# NorthStar_SuperCap_V0_2.net
KiCad netlist of a schematic drawn in EAGLE
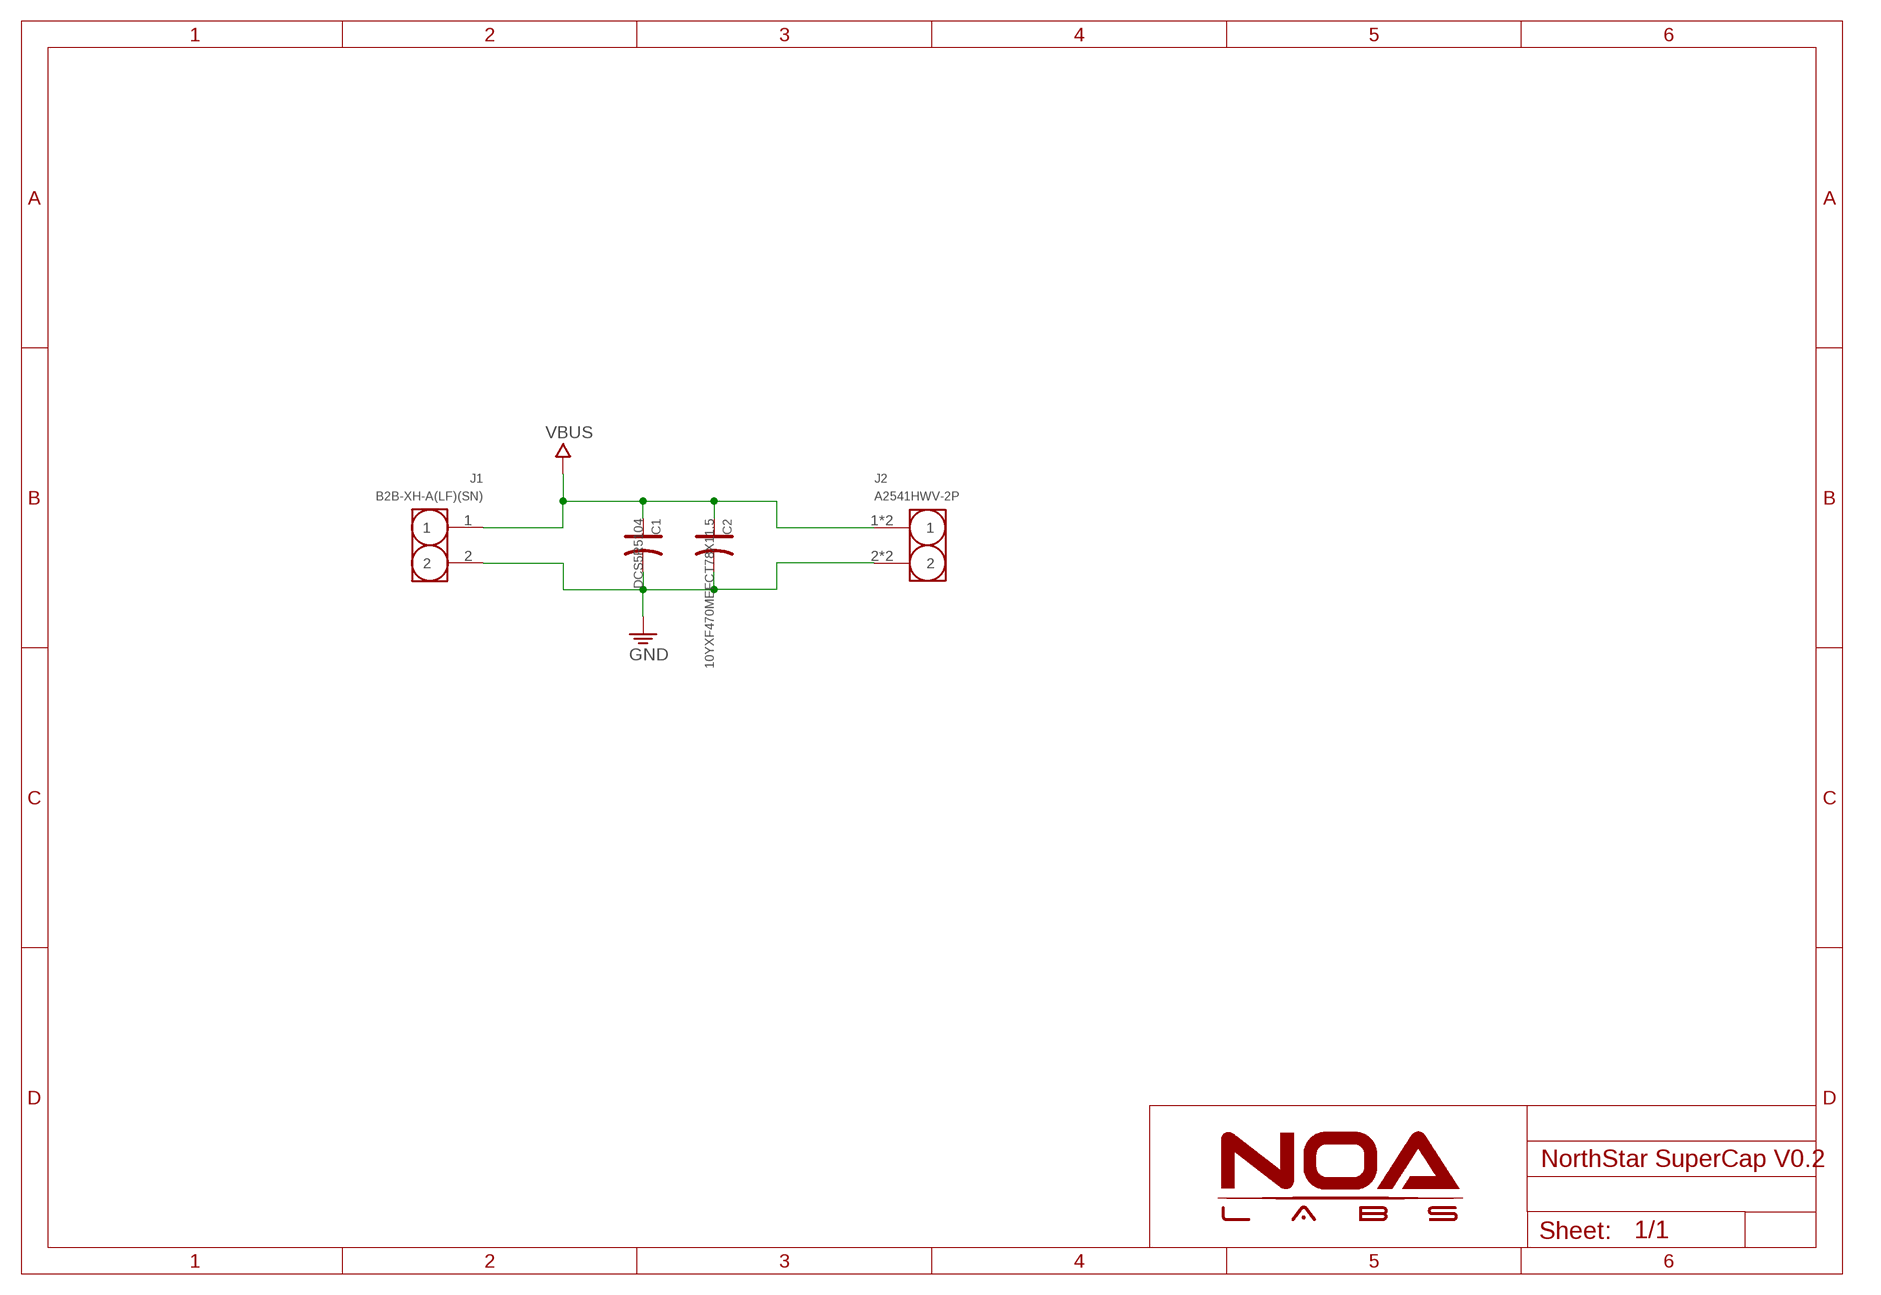
[diagram p0: schematic, sheet 1]

(export (version "E")
  (design (tool "Eeschema 10.0.6"))
  (components
    (comp (ref "C1")
      (value "DCS5R5104")
      (footprint "eagle-import:11.5X5.5MM-P10")
      (libsource (lib "eagle-import") (part "CAP-H-TYPE"))
    )
    (comp (ref "C2")
      (value "10YXF470MEFCT78X11.5")
      (footprint "eagle-import:ELECTRO-8.0MM")
      (libsource (lib "eagle-import") (part "CAP-D8.0/3.81"))
    )
    (comp (ref "J1")
      (value "B2B-XH-A(LF)(SN)")
      (footprint "eagle-import:XH-02-90")
      (libsource (lib "eagle-import") (part "HEADER-2P-90DEG-FEMALE"))
    )
    (comp (ref "J2")
      (value "A2541HWV-2P")
      (footprint "eagle-import:2P-2.54-BOTTOM-ENTRY")
      (libsource (lib "eagle-import") (part "HEADER-2P-FEMALE"))
    )
  )
  (nets
    (net (code "1") (name "GND") (class "Default")
      (node (ref "C1") (pin "2") (pinfunction "-_2") (pintype "passive"))
      (node (ref "C2") (pin "-") (pinfunction "-_-") (pintype "passive"))
      (node (ref "J1") (pin "2") (pinfunction "2_2") (pintype "bidirectional"))
      (node (ref "J2") (pin "2") (pinfunction "2_2") (pintype "bidirectional"))
      (node (ref "J2") (pin "2-2") (pinfunction "2_2-2") (pintype "bidirectional"))
    )
    (net (code "2") (name "VBUS") (class "Default")
      (node (ref "C1") (pin "1") (pinfunction "+_1") (pintype "passive"))
      (node (ref "C2") (pin "+") (pinfunction "+_+") (pintype "passive"))
      (node (ref "J1") (pin "1") (pinfunction "1_1") (pintype "bidirectional"))
      (node (ref "J2") (pin "1") (pinfunction "1_1") (pintype "bidirectional"))
      (node (ref "J2") (pin "1-1") (pinfunction "1_1-1") (pintype "bidirectional"))
    )
  )
)
